# electronics.net
KiCad netlist of a schematic drawn in EAGLE
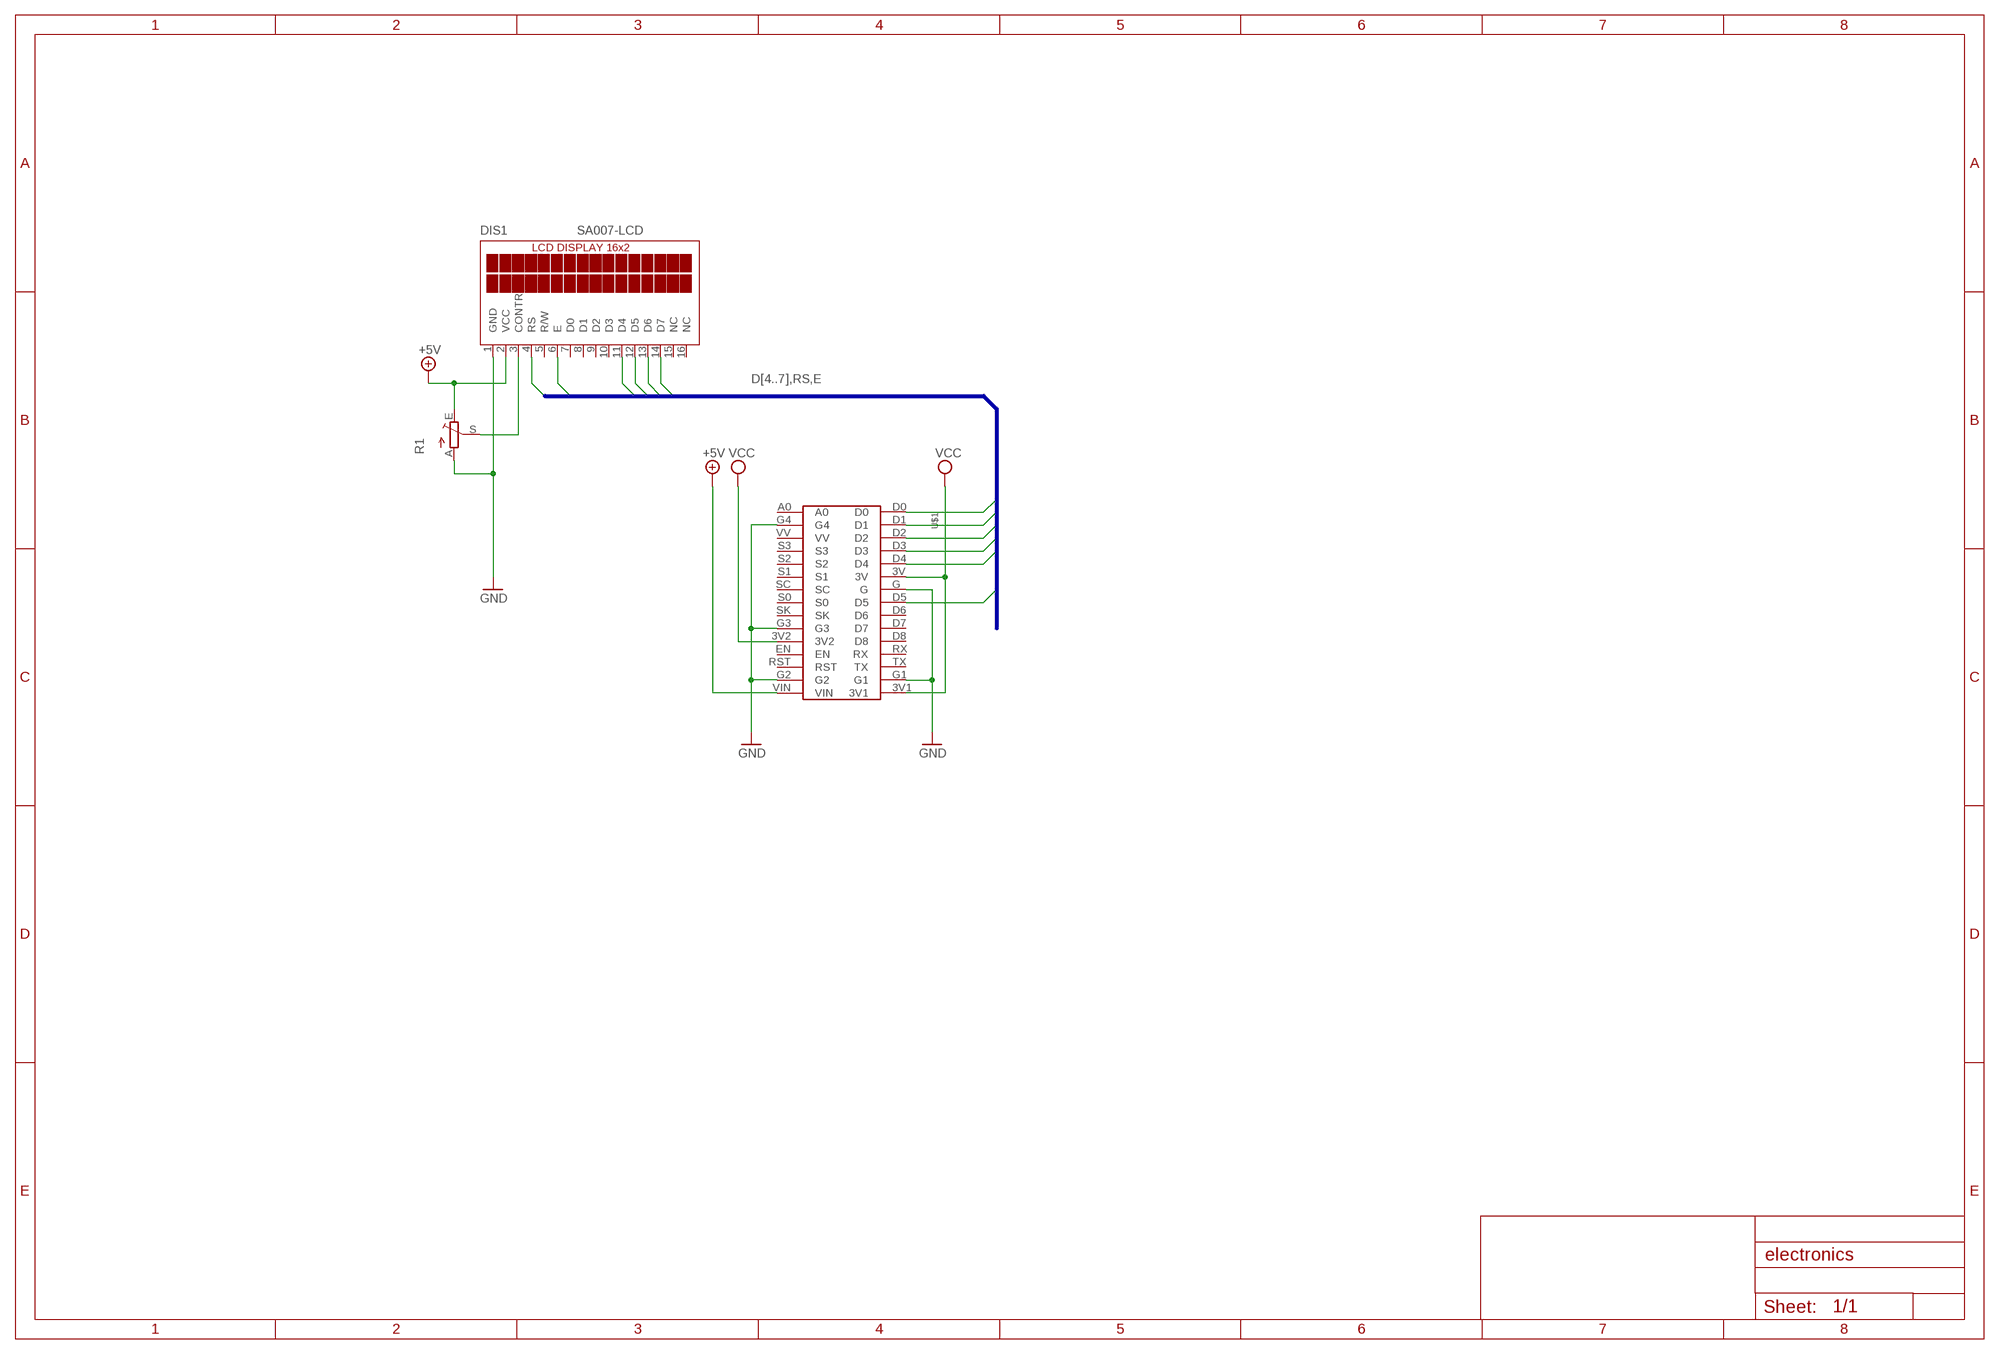
[diagram p0: schematic, sheet 1]

(export (version "E")
  (design (tool "Eeschema 10.0.6"))
  (components
    (comp (ref "DIS1")
      (value "SA007-LCD")
      (footprint "eagle-import:SA007-LCD")
      (libsource (lib "eagle-import") (part "SA007-LCD"))
    )
    (comp (ref "R1")
      (value "TRIM_EU-CA9H")
      (footprint "eagle-import:CA9H")
      (libsource (lib "eagle-import") (part "TRIM_EU-CA9H"))
    )
    (comp (ref "U$1")
      (value "LOLIN")
      (footprint "eagle-import:LOLIN")
      (libsource (lib "eagle-import") (part "LOLIN"))
    )
  )
  (nets
    (net (code "1") (name "+5V") (class "Default")
      (node (ref "DIS1") (pin "2") (pinfunction "VCC_2") (pintype "power_in"))
      (node (ref "R1") (pin "E") (pinfunction "E_E") (pintype "passive"))
      (node (ref "U$1") (pin "VIN") (pinfunction "VIN_VIN") (pintype "bidirectional"))
    )
    (net (code "2") (name "/D4") (class "Default")
      (node (ref "DIS1") (pin "11") (pinfunction "D4_11") (pintype "input"))
      (node (ref "U$1") (pin "D0") (pinfunction "D0_D0") (pintype "bidirectional"))
    )
    (net (code "3") (name "/D5") (class "Default")
      (node (ref "DIS1") (pin "12") (pinfunction "D5_12") (pintype "input"))
      (node (ref "U$1") (pin "D1") (pinfunction "D1_D1") (pintype "bidirectional"))
    )
    (net (code "4") (name "/D6") (class "Default")
      (node (ref "DIS1") (pin "13") (pinfunction "D6_13") (pintype "input"))
      (node (ref "U$1") (pin "D2") (pinfunction "D2_D2") (pintype "bidirectional"))
    )
    (net (code "5") (name "/D7") (class "Default")
      (node (ref "DIS1") (pin "14") (pinfunction "D7_14") (pintype "input"))
      (node (ref "U$1") (pin "D3") (pinfunction "D3_D3") (pintype "bidirectional"))
    )
    (net (code "6") (name "/E") (class "Default")
      (node (ref "DIS1") (pin "6") (pinfunction "E_6") (pintype "input"))
      (node (ref "U$1") (pin "D5") (pinfunction "D5_D5") (pintype "bidirectional"))
    )
    (net (code "7") (name "/RS") (class "Default")
      (node (ref "DIS1") (pin "4") (pinfunction "RS_4") (pintype "input"))
      (node (ref "U$1") (pin "D4") (pinfunction "D4_D4") (pintype "bidirectional"))
    )
    (net (code "9") (name "GND") (class "Default")
      (node (ref "DIS1") (pin "1") (pinfunction "GND_1") (pintype "power_in"))
      (node (ref "R1") (pin "A") (pinfunction "A_A") (pintype "passive"))
      (node (ref "U$1") (pin "G") (pinfunction "G_G") (pintype "bidirectional"))
      (node (ref "U$1") (pin "G1") (pinfunction "G1_G1") (pintype "bidirectional"))
      (node (ref "U$1") (pin "G2") (pinfunction "G2_G2") (pintype "bidirectional"))
      (node (ref "U$1") (pin "G3") (pinfunction "G3_G3") (pintype "bidirectional"))
      (node (ref "U$1") (pin "G4") (pinfunction "G4_G4") (pintype "bidirectional"))
    )
    (net (code "10") (name "Net-(DIS1-CONTR)") (class "Default")
      (node (ref "DIS1") (pin "3") (pinfunction "CONTR_3") (pintype "input"))
      (node (ref "R1") (pin "S") (pinfunction "S_S") (pintype "passive"))
    )
    (net (code "11") (name "VCC") (class "Default")
      (node (ref "U$1") (pin "3V") (pinfunction "3V_3V") (pintype "bidirectional"))
      (node (ref "U$1") (pin "3V1") (pinfunction "3V1_3V1") (pintype "bidirectional"))
      (node (ref "U$1") (pin "3V2") (pinfunction "3V2_3V2") (pintype "bidirectional"))
    )
    (net (code "12") (name "unconnected-(DIS1-D0-Pad7)") (class "Default")
      (node (ref "DIS1") (pin "7") (pinfunction "D0_7") (pintype "input"))
    )
    (net (code "13") (name "unconnected-(DIS1-D1-Pad8)") (class "Default")
      (node (ref "DIS1") (pin "8") (pinfunction "D1_8") (pintype "input"))
    )
    (net (code "14") (name "unconnected-(DIS1-D2-Pad9)") (class "Default")
      (node (ref "DIS1") (pin "9") (pinfunction "D2_9") (pintype "input"))
    )
    (net (code "15") (name "unconnected-(DIS1-D3-Pad10)") (class "Default")
      (node (ref "DIS1") (pin "10") (pinfunction "D3_10") (pintype "input"))
    )
    (net (code "16") (name "unconnected-(DIS1-NC-Pad15)") (class "Default")
      (node (ref "DIS1") (pin "15") (pinfunction "NC_15") (pintype "no_connect"))
    )
    (net (code "17") (name "unconnected-(DIS1-NC-Pad16)") (class "Default")
      (node (ref "DIS1") (pin "16") (pinfunction "NC_16") (pintype "no_connect"))
    )
    (net (code "18") (name "unconnected-(DIS1-R{slash}W-Pad5)") (class "Default")
      (node (ref "DIS1") (pin "5") (pinfunction "R/W_5") (pintype "input"))
    )
    (net (code "19") (name "unconnected-(U$1-PadA0)") (class "Default")
      (node (ref "U$1") (pin "A0") (pinfunction "A0_A0") (pintype "bidirectional"))
    )
    (net (code "20") (name "unconnected-(U$1-PadD6)") (class "Default")
      (node (ref "U$1") (pin "D6") (pinfunction "D6_D6") (pintype "bidirectional"))
    )
    (net (code "21") (name "unconnected-(U$1-PadD7)") (class "Default")
      (node (ref "U$1") (pin "D7") (pinfunction "D7_D7") (pintype "bidirectional"))
    )
    (net (code "22") (name "unconnected-(U$1-PadD8)") (class "Default")
      (node (ref "U$1") (pin "D8") (pinfunction "D8_D8") (pintype "bidirectional"))
    )
    (net (code "23") (name "unconnected-(U$1-PadEN)") (class "Default")
      (node (ref "U$1") (pin "EN") (pinfunction "EN_EN") (pintype "bidirectional"))
    )
    (net (code "24") (name "unconnected-(U$1-PadRST)") (class "Default")
      (node (ref "U$1") (pin "RST") (pinfunction "RST_RST") (pintype "bidirectional"))
    )
    (net (code "25") (name "unconnected-(U$1-PadRX)") (class "Default")
      (node (ref "U$1") (pin "RX") (pinfunction "RX_RX") (pintype "bidirectional"))
    )
    (net (code "26") (name "unconnected-(U$1-PadS0)") (class "Default")
      (node (ref "U$1") (pin "S0") (pinfunction "S0_S0") (pintype "bidirectional"))
    )
    (net (code "27") (name "unconnected-(U$1-PadS1)") (class "Default")
      (node (ref "U$1") (pin "S1") (pinfunction "S1_S1") (pintype "bidirectional"))
    )
    (net (code "28") (name "unconnected-(U$1-PadS2)") (class "Default")
      (node (ref "U$1") (pin "S2") (pinfunction "S2_S2") (pintype "bidirectional"))
    )
    (net (code "29") (name "unconnected-(U$1-PadS3)") (class "Default")
      (node (ref "U$1") (pin "S3") (pinfunction "S3_S3") (pintype "bidirectional"))
    )
    (net (code "30") (name "unconnected-(U$1-PadSC)") (class "Default")
      (node (ref "U$1") (pin "SC") (pinfunction "SC_SC") (pintype "bidirectional"))
    )
    (net (code "31") (name "unconnected-(U$1-PadSK)") (class "Default")
      (node (ref "U$1") (pin "SK") (pinfunction "SK_SK") (pintype "bidirectional"))
    )
    (net (code "32") (name "unconnected-(U$1-PadTX)") (class "Default")
      (node (ref "U$1") (pin "TX") (pinfunction "TX_TX") (pintype "bidirectional"))
    )
    (net (code "33") (name "unconnected-(U$1-PadVV)") (class "Default")
      (node (ref "U$1") (pin "VV") (pinfunction "VV_VV") (pintype "bidirectional"))
    )
  )
)
